# LB_BIT_i12_TEMPSENSOR-v02_rev1.net
KiCad netlist of a schematic drawn in EAGLE
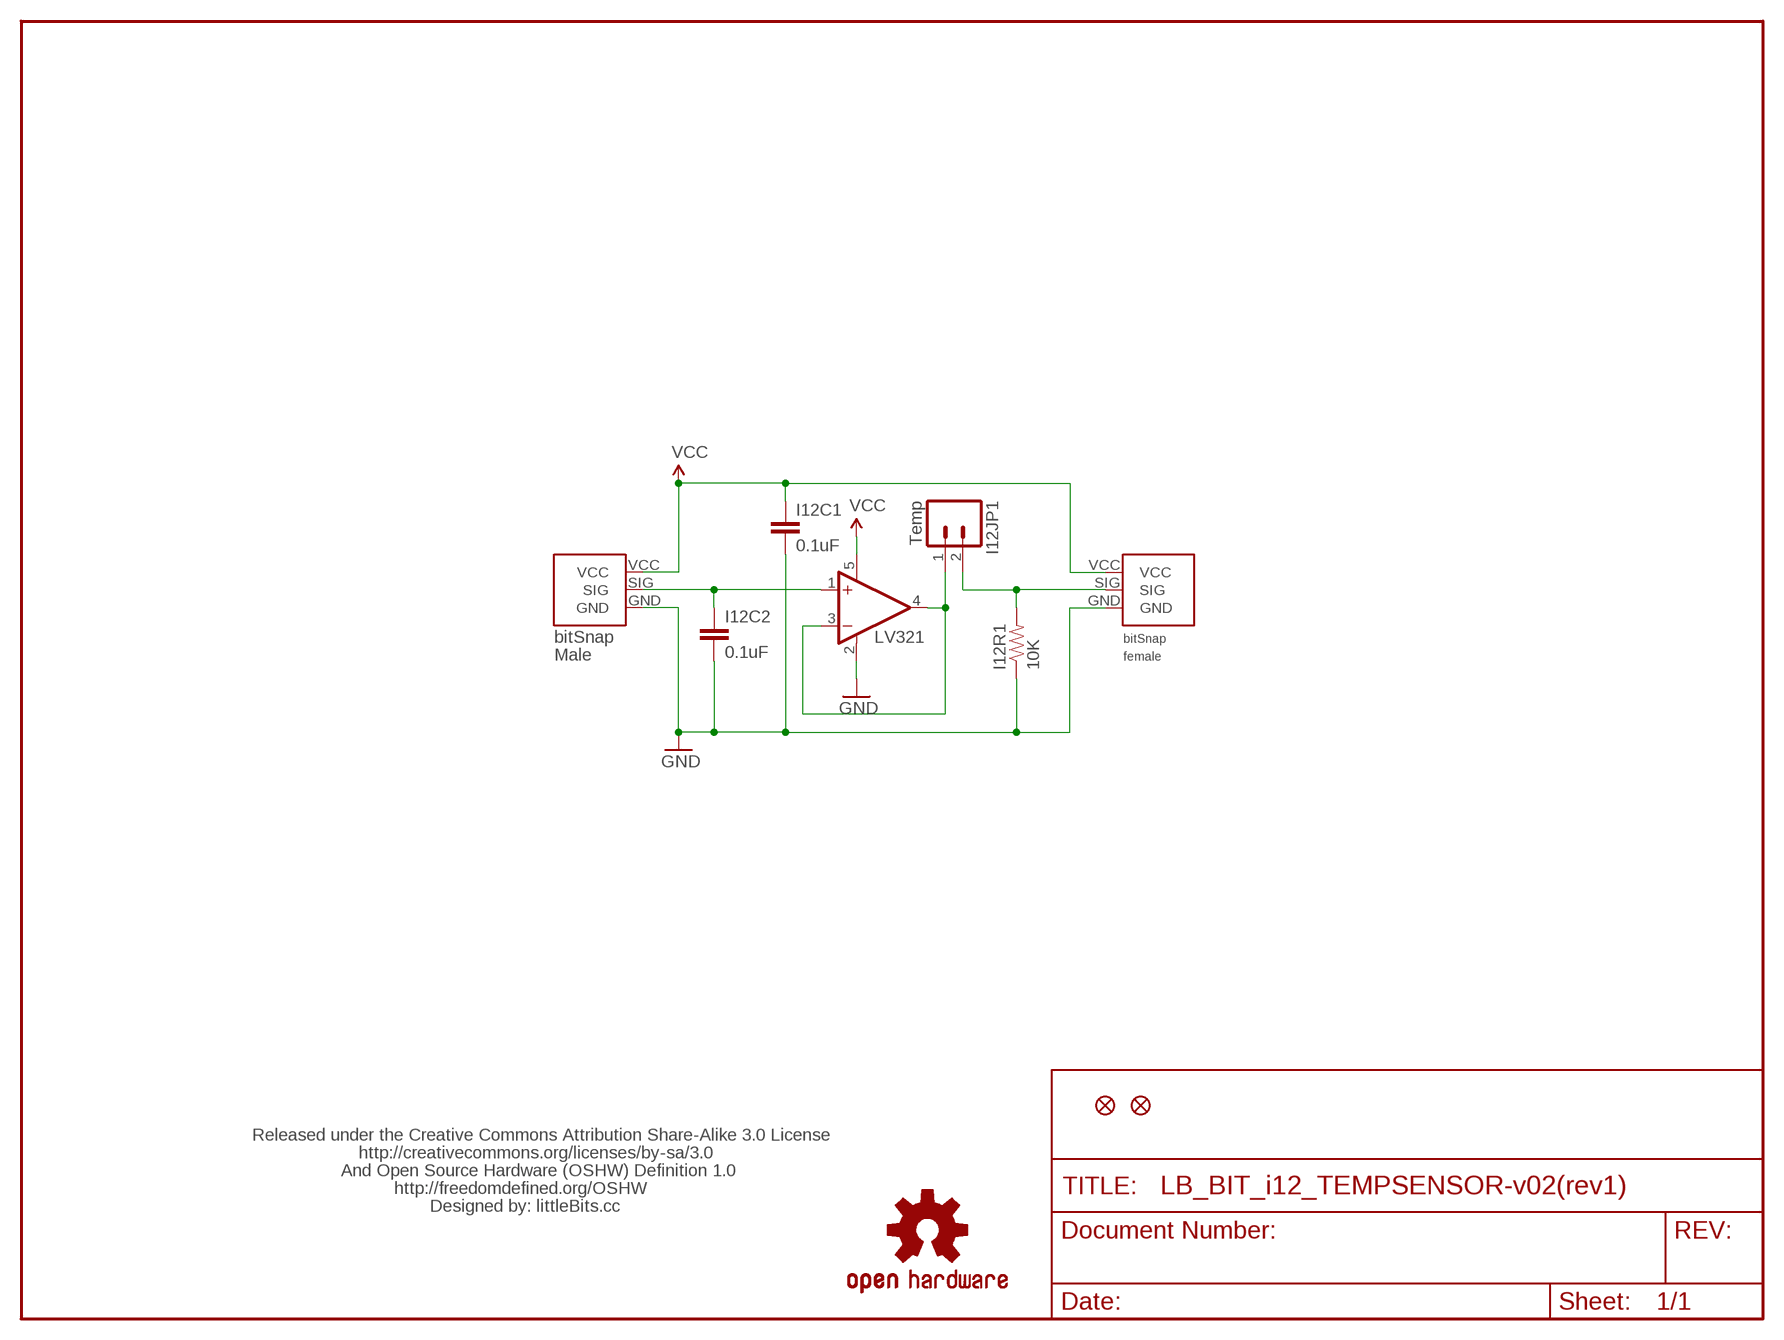
[diagram p0: schematic, sheet 1]

(export (version "E")
  (design (tool "Eeschema 10.0.6"))
  (components
    (comp (ref "I12BSF")
      (value "BITSNAP_FEMALE")
      (footprint "eagle-import:BITSNAP_FEMALE")
      (libsource (lib "eagle-import") (part "BITSNAP_FEMALE"))
    )
    (comp (ref "I12BSM")
      (value "BITSNAP_MALE")
      (footprint "eagle-import:BITSNAP_MALE")
      (libsource (lib "eagle-import") (part "BITSNAP_MALE"))
    )
    (comp (ref "I12C1")
      (value "0.1uF")
      (footprint "eagle-import:0603-CAP")
      (libsource (lib "eagle-import") (part "CAP0603-CAP"))
    )
    (comp (ref "I12C2")
      (value "0.1uF")
      (footprint "eagle-import:0603-CAP")
      (libsource (lib "eagle-import") (part "CAP0603-CAP"))
    )
    (comp (ref "I12JP1")
      (value "Temp")
      (footprint "eagle-import:1X02")
      (libsource (lib "eagle-import") (part "M02PTH"))
    )
    (comp (ref "I12R1")
      (value "10K")
      (footprint "eagle-import:0603-RES")
      (libsource (lib "eagle-import") (part "RESISTOR0603-RES"))
    )
    (comp (ref "I12U1")
      (value "LV321")
      (footprint "eagle-import:SC70")
      (libsource (lib "eagle-import") (part "LV321"))
    )
    (comp (ref "JP2")
      (value "FIDUCIAL1X2")
      (footprint "eagle-import:FIDUCIAL-1X2")
      (libsource (lib "eagle-import") (part "FIDUCIAL1X2"))
    )
    (comp (ref "JP3")
      (value "FIDUCIAL1X2")
      (footprint "eagle-import:FIDUCIAL-1X2")
      (libsource (lib "eagle-import") (part "FIDUCIAL1X2"))
    )
    (comp (ref "U$1")
      (value "OSHW-LOGOL")
      (footprint "eagle-import:OSHW-LOGO-L")
      (libsource (lib "eagle-import") (part "OSHW-LOGOL"))
    )
    (comp (ref "U$18")
      (value "LB_CREDITS_V2")
      (footprint "eagle-import:LB_CREDITS_V2")
      (libsource (lib "eagle-import") (part "LB_CREDITS_V2"))
    )
  )
  (nets
    (net (code "1") (name "GND") (class "Default")
      (node (ref "I12BSF") (pin "GND") (pinfunction "GND_GND") (pintype "bidirectional"))
      (node (ref "I12BSM") (pin "GND") (pinfunction "GND_GND") (pintype "bidirectional"))
      (node (ref "I12C1") (pin "2") (pinfunction "2_2") (pintype "passive"))
      (node (ref "I12C2") (pin "2") (pinfunction "2_2") (pintype "passive"))
      (node (ref "I12R1") (pin "1") (pinfunction "1_1") (pintype "passive"))
      (node (ref "I12U1") (pin "2") (pinfunction "V-_2") (pintype "power_in"))
    )
    (net (code "2") (name "Net-(I12BSF-PadSIG)") (class "Default")
      (node (ref "I12BSF") (pin "SIG") (pinfunction "SIG_SIG") (pintype "bidirectional"))
      (node (ref "I12JP1") (pin "2") (pinfunction "2_2") (pintype "passive"))
      (node (ref "I12R1") (pin "2") (pinfunction "2_2") (pintype "passive"))
    )
    (net (code "3") (name "Net-(I12U1-+IN)") (class "Default")
      (node (ref "I12BSM") (pin "SIG") (pinfunction "SIG_SIG") (pintype "bidirectional"))
      (node (ref "I12C2") (pin "1") (pinfunction "1_1") (pintype "passive"))
      (node (ref "I12U1") (pin "1") (pinfunction "+IN_1") (pintype "input"))
    )
    (net (code "4") (name "Net-(I12U1--IN)") (class "Default")
      (node (ref "I12JP1") (pin "1") (pinfunction "1_1") (pintype "passive"))
      (node (ref "I12U1") (pin "3") (pinfunction "-IN_3") (pintype "input"))
      (node (ref "I12U1") (pin "4") (pinfunction "OUT_4") (pintype "output"))
    )
    (net (code "5") (name "VCC") (class "Default")
      (node (ref "I12BSF") (pin "VCC") (pinfunction "VCC_VCC") (pintype "bidirectional"))
      (node (ref "I12BSM") (pin "VCC") (pinfunction "VCC_VCC") (pintype "bidirectional"))
      (node (ref "I12C1") (pin "1") (pinfunction "1_1") (pintype "passive"))
      (node (ref "I12U1") (pin "5") (pinfunction "V+_5") (pintype "power_in"))
    )
  )
)
